# servopoinB-2.net
KiCad netlist of a schematic drawn in EAGLE
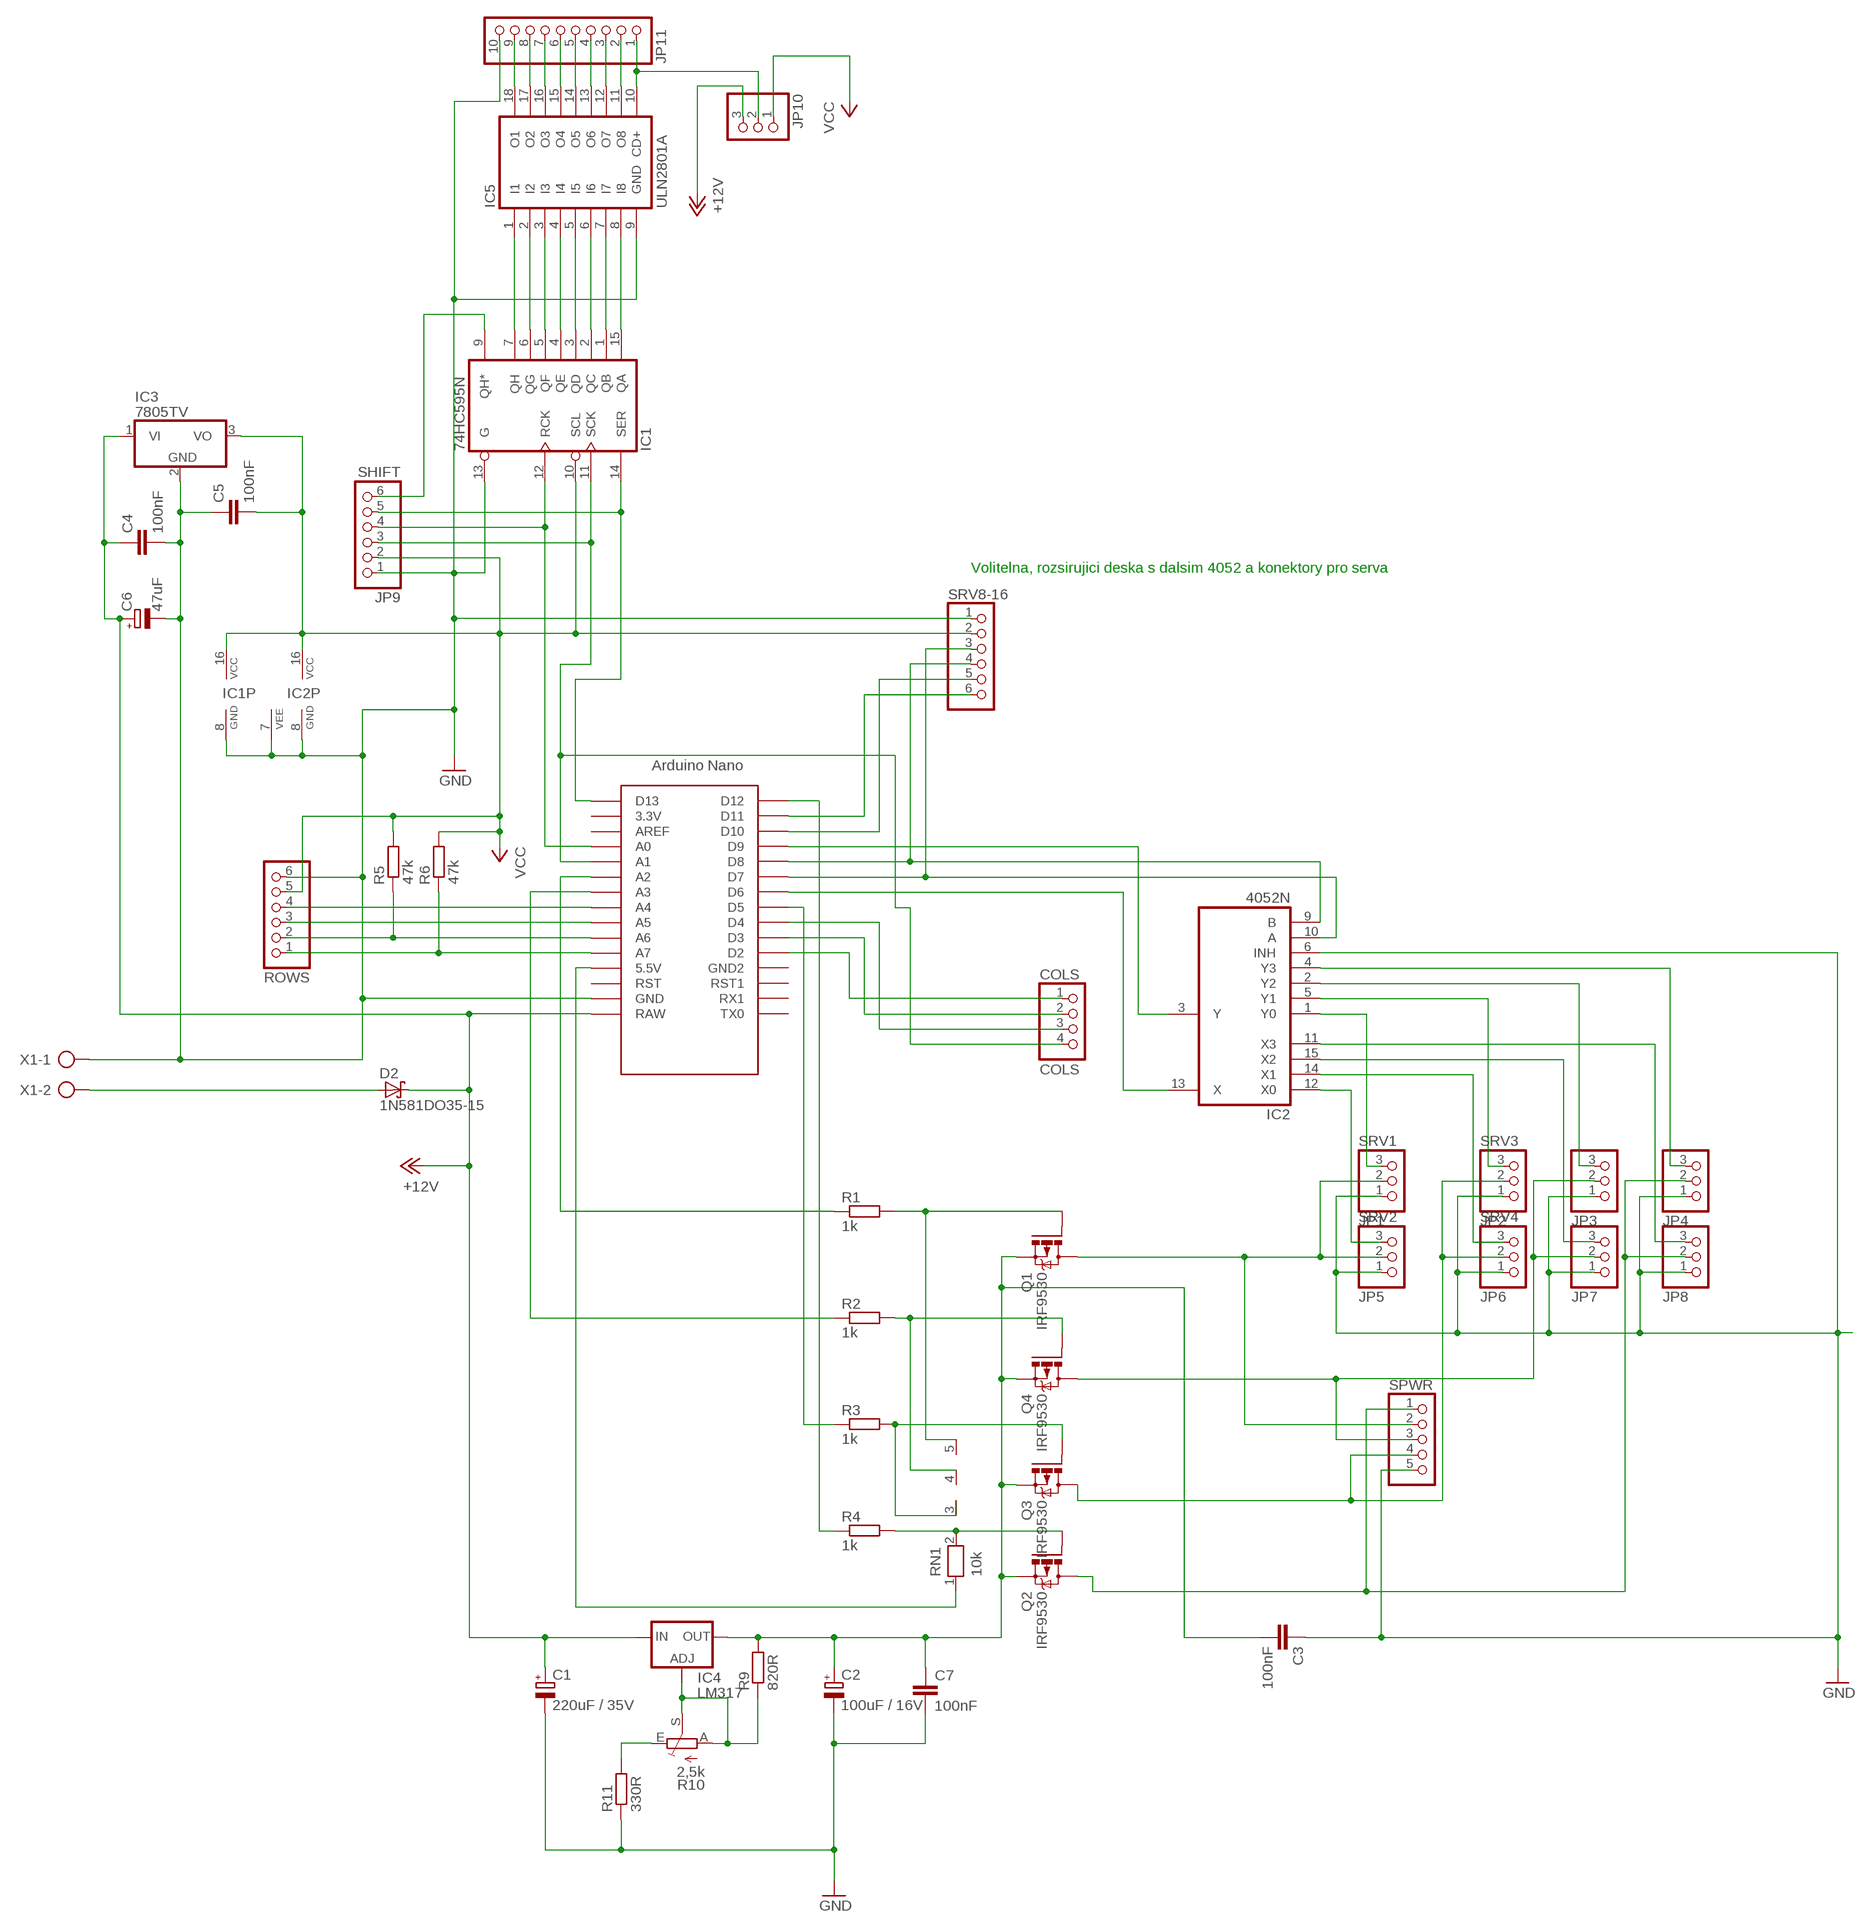
[diagram p0: schematic, sheet 1]

(export (version "E")
  (design (tool "Eeschema 10.0.6"))
  (components
    (comp (ref "C1")
      (value "220uF / 35V")
      (footprint "eagle-import:E5-10,5")
      (libsource (lib "eagle-import") (part "resistor_CPOL-EUE5-10.5"))
    )
    (comp (ref "C2")
      (value "100uF / 16V")
      (footprint "eagle-import:E2,5-5")
      (libsource (lib "eagle-import") (part "resistor_CPOL-EUE2.5-5"))
    )
    (comp (ref "C3")
      (value "100nF")
      (footprint "eagle-import:C025-025X050")
      (libsource (lib "eagle-import") (part "resistor_C-EU025-025X050"))
    )
    (comp (ref "C4")
      (value "100nF")
      (footprint "eagle-import:C025-025X050")
      (libsource (lib "eagle-import") (part "C-EU025-025X050"))
    )
    (comp (ref "C5")
      (value "100nF")
      (footprint "eagle-import:C025-025X050")
      (libsource (lib "eagle-import") (part "C-EU025-025X050"))
    )
    (comp (ref "C6")
      (value "47uF")
      (footprint "eagle-import:E2,5-6")
      (libsource (lib "eagle-import") (part "CPOL-EUE2.5-6"))
    )
    (comp (ref "C7")
      (value "100nF")
      (footprint "eagle-import:C025-025X050")
      (libsource (lib "eagle-import") (part "resistor_C-EU025-025X050"))
    )
    (comp (ref "COLS")
      (value "COLS")
      (footprint "eagle-import:1X04")
      (libsource (lib "eagle-import") (part "PINHD-1X4"))
    )
    (comp (ref "D2")
      (value "1N581DO35-15")
      (footprint "eagle-import:DO35-10")
      (libsource (lib "eagle-import") (part "1N581DO35-15"))
    )
    (comp (ref "IC1")
      (value "74HC595N")
      (footprint "eagle-import:DIL16")
      (libsource (lib "eagle-import") (part "74595NHC"))
    )
    (comp (ref "IC2")
      (value "4052N")
      (footprint "eagle-import:DIL16")
      (libsource (lib "eagle-import") (part "4052N"))
    )
    (comp (ref "IC3")
      (value "7805TV")
      (footprint "eagle-import:TO220V")
      (libsource (lib "eagle-import") (part "78TV05"))
    )
    (comp (ref "IC4")
      (value "LM317")
      (footprint "eagle-import:317TS")
      (libsource (lib "eagle-import") (part "LM317TS"))
    )
    (comp (ref "IC5")
      (value "ULN2801A")
      (footprint "eagle-import:DIL18")
      (libsource (lib "eagle-import") (part "ULN2801A"))
    )
    (comp (ref "JP1")
      (value "SRV1")
      (footprint "eagle-import:1X03")
      (libsource (lib "eagle-import") (part "PINHD-1X3"))
    )
    (comp (ref "JP2")
      (value "SRV3")
      (footprint "eagle-import:1X03")
      (libsource (lib "eagle-import") (part "PINHD-1X3"))
    )
    (comp (ref "JP3")
      (value "PINHD-1X3")
      (footprint "eagle-import:1X03")
      (libsource (lib "eagle-import") (part "PINHD-1X3"))
    )
    (comp (ref "JP4")
      (value "PINHD-1X3")
      (footprint "eagle-import:1X03")
      (libsource (lib "eagle-import") (part "PINHD-1X3"))
    )
    (comp (ref "JP5")
      (value "SRV2")
      (footprint "eagle-import:1X03")
      (libsource (lib "eagle-import") (part "PINHD-1X3"))
    )
    (comp (ref "JP6")
      (value "SRV4")
      (footprint "eagle-import:1X03")
      (libsource (lib "eagle-import") (part "PINHD-1X3"))
    )
    (comp (ref "JP7")
      (value "PINHD-1X3")
      (footprint "eagle-import:1X03")
      (libsource (lib "eagle-import") (part "PINHD-1X3"))
    )
    (comp (ref "JP8")
      (value "PINHD-1X3")
      (footprint "eagle-import:1X03")
      (libsource (lib "eagle-import") (part "PINHD-1X3"))
    )
    (comp (ref "JP9")
      (value "SHIFT")
      (footprint "eagle-import:1X06")
      (libsource (lib "eagle-import") (part "PINHD-1X6"))
    )
    (comp (ref "JP10")
      (value "PINHD-1X3")
      (footprint "eagle-import:1X03")
      (libsource (lib "eagle-import") (part "PINHD-1X3"))
    )
    (comp (ref "JP11")
      (value "PINHD-1X10")
      (footprint "eagle-import:1X10")
      (libsource (lib "eagle-import") (part "PINHD-1X10"))
    )
    (comp (ref "Q1")
      (value "IRF9530")
      (footprint "eagle-import:TO220BV")
      (libsource (lib "eagle-import") (part "IRF9530"))
    )
    (comp (ref "Q2")
      (value "IRF9530")
      (footprint "eagle-import:TO220BV")
      (libsource (lib "eagle-import") (part "IRF9530"))
    )
    (comp (ref "Q3")
      (value "IRF9530")
      (footprint "eagle-import:TO220BV")
      (libsource (lib "eagle-import") (part "IRF9530"))
    )
    (comp (ref "Q4")
      (value "IRF9530")
      (footprint "eagle-import:TO220BV")
      (libsource (lib "eagle-import") (part "IRF9530"))
    )
    (comp (ref "R1")
      (value "1k")
      (footprint "eagle-import:0207_10")
      (libsource (lib "eagle-import") (part "R-EU_0207/10"))
    )
    (comp (ref "R2")
      (value "1k")
      (footprint "eagle-import:0207_10")
      (libsource (lib "eagle-import") (part "R-EU_0207/10"))
    )
    (comp (ref "R3")
      (value "1k")
      (footprint "eagle-import:0207_10")
      (libsource (lib "eagle-import") (part "R-EU_0207/10"))
    )
    (comp (ref "R4")
      (value "1k")
      (footprint "eagle-import:0207_10")
      (libsource (lib "eagle-import") (part "R-EU_0207/10"))
    )
    (comp (ref "R5")
      (value "47k")
      (footprint "eagle-import:0207_10")
      (libsource (lib "eagle-import") (part "R-EU_0207/10"))
    )
    (comp (ref "R6")
      (value "47k")
      (footprint "eagle-import:0207_10")
      (libsource (lib "eagle-import") (part "R-EU_0207/10"))
    )
    (comp (ref "R9")
      (value "820R")
      (footprint "eagle-import:0207_10")
      (libsource (lib "eagle-import") (part "R-EU_0207/10"))
    )
    (comp (ref "R10")
      (value "2,5k")
      (footprint "eagle-import:LI10")
      (libsource (lib "eagle-import") (part "TRIM_EU-LI10-PADS"))
    )
    (comp (ref "R11")
      (value "330R")
      (footprint "eagle-import:0207_10")
      (libsource (lib "eagle-import") (part "R-EU_0207/10"))
    )
    (comp (ref "RN1")
      (value "10k")
      (footprint "eagle-import:RN-5")
      (libsource (lib "eagle-import") (part "RN04"))
    )
    (comp (ref "ROWS")
      (value "PINHD-1X6")
      (footprint "eagle-import:1X06")
      (libsource (lib "eagle-import") (part "PINHD-1X6"))
    )
    (comp (ref "SPWR")
      (value "PINHD-1X5")
      (footprint "eagle-import:1X05")
      (libsource (lib "eagle-import") (part "PINHD-1X5"))
    )
    (comp (ref "SRV8-16")
      (value "PINHD-1X6")
      (footprint "eagle-import:1X06")
      (libsource (lib "eagle-import") (part "PINHD-1X6"))
    )
    (comp (ref "U$1")
      (value "NANO")
      (footprint "eagle-import:NANO")
      (libsource (lib "eagle-import") (part "NANO"))
    )
    (comp (ref "X1")
      (value "AK500/2")
      (footprint "eagle-import:AK500_2")
      (libsource (lib "eagle-import") (part "AK500/2"))
    )
  )
  (nets
    (net (code "1") (name "+12V") (class "Default")
      (node (ref "C1") (pin "+") (pinfunction "+_+") (pintype "passive"))
      (node (ref "C4") (pin "1") (pinfunction "1_1") (pintype "passive"))
      (node (ref "C6") (pin "+") (pinfunction "+_+") (pintype "passive"))
      (node (ref "D2") (pin "C") (pinfunction "C_C") (pintype "passive"))
      (node (ref "IC3") (pin "1") (pinfunction "VI_1") (pintype "input"))
      (node (ref "IC4") (pin "3") (pinfunction "IN_3") (pintype "input"))
      (node (ref "JP10") (pin "3") (pinfunction "3_3") (pintype "passive"))
      (node (ref "U$1") (pin "RAW") (pinfunction "RAW_RAW") (pintype "bidirectional"))
    )
    (net (code "2") (name "GND") (class "Default")
      (node (ref "C1") (pin "-") (pinfunction "-_-") (pintype "passive"))
      (node (ref "C2") (pin "-") (pinfunction "-_-") (pintype "passive"))
      (node (ref "C3") (pin "1") (pinfunction "1_1") (pintype "passive"))
      (node (ref "C4") (pin "2") (pinfunction "2_2") (pintype "passive"))
      (node (ref "C5") (pin "1") (pinfunction "1_1") (pintype "passive"))
      (node (ref "C6") (pin "-") (pinfunction "-_-") (pintype "passive"))
      (node (ref "C7") (pin "2") (pinfunction "2_2") (pintype "passive"))
      (node (ref "IC1") (pin "13") (pinfunction "G_13") (pintype "input"))
      (node (ref "IC1") (pin "8") (pinfunction "GND_8") (pintype "power_in"))
      (node (ref "IC2") (pin "6") (pinfunction "INH_6") (pintype "input"))
      (node (ref "IC2") (pin "7") (pinfunction "VEE_7") (pintype "power_in"))
      (node (ref "IC2") (pin "8") (pinfunction "GND_8") (pintype "power_in"))
      (node (ref "IC3") (pin "2") (pinfunction "GND_2") (pintype "passive"))
      (node (ref "IC5") (pin "9") (pinfunction "GND_9") (pintype "power_in"))
      (node (ref "JP1") (pin "1") (pinfunction "1_1") (pintype "passive"))
      (node (ref "JP11") (pin "10") (pinfunction "10_10") (pintype "passive"))
      (node (ref "JP2") (pin "1") (pinfunction "1_1") (pintype "passive"))
      (node (ref "JP3") (pin "1") (pinfunction "1_1") (pintype "passive"))
      (node (ref "JP4") (pin "1") (pinfunction "1_1") (pintype "passive"))
      (node (ref "JP5") (pin "1") (pinfunction "1_1") (pintype "passive"))
      (node (ref "JP6") (pin "1") (pinfunction "1_1") (pintype "passive"))
      (node (ref "JP7") (pin "1") (pinfunction "1_1") (pintype "passive"))
      (node (ref "JP8") (pin "1") (pinfunction "1_1") (pintype "passive"))
      (node (ref "JP9") (pin "1") (pinfunction "1_1") (pintype "passive"))
      (node (ref "R11") (pin "1") (pinfunction "1_1") (pintype "passive"))
      (node (ref "ROWS") (pin "6") (pinfunction "6_6") (pintype "passive"))
      (node (ref "SPWR") (pin "5") (pinfunction "5_5") (pintype "passive"))
      (node (ref "SRV8-16") (pin "1") (pinfunction "1_1") (pintype "passive"))
      (node (ref "U$1") (pin "GND") (pinfunction "GND_GND") (pintype "bidirectional"))
      (node (ref "X1") (pin "1") (pinfunction "KL_1") (pintype "passive"))
    )
    (net (code "3") (name "Net-(COLS-Pad1)") (class "Default")
      (node (ref "COLS") (pin "1") (pinfunction "1_1") (pintype "passive"))
      (node (ref "U$1") (pin "D2") (pinfunction "D2_D2") (pintype "bidirectional"))
    )
    (net (code "4") (name "Net-(COLS-Pad2)") (class "Default")
      (node (ref "COLS") (pin "2") (pinfunction "2_2") (pintype "passive"))
      (node (ref "U$1") (pin "D3") (pinfunction "D3_D3") (pintype "bidirectional"))
    )
    (net (code "5") (name "Net-(COLS-Pad3)") (class "Default")
      (node (ref "COLS") (pin "3") (pinfunction "3_3") (pintype "passive"))
      (node (ref "U$1") (pin "D4") (pinfunction "D4_D4") (pintype "bidirectional"))
    )
    (net (code "6") (name "Net-(IC1A-QA)") (class "Default")
      (node (ref "IC1") (pin "15") (pinfunction "QA_15") (pintype "tri_state"))
      (node (ref "IC5") (pin "8") (pinfunction "I8_8") (pintype "input"))
    )
    (net (code "7") (name "Net-(IC1A-QB)") (class "Default")
      (node (ref "IC1") (pin "1") (pinfunction "QB_1") (pintype "tri_state"))
      (node (ref "IC5") (pin "7") (pinfunction "I7_7") (pintype "input"))
    )
    (net (code "8") (name "Net-(IC1A-QC)") (class "Default")
      (node (ref "IC1") (pin "2") (pinfunction "QC_2") (pintype "tri_state"))
      (node (ref "IC5") (pin "6") (pinfunction "I6_6") (pintype "input"))
    )
    (net (code "9") (name "Net-(IC1A-QD)") (class "Default")
      (node (ref "IC1") (pin "3") (pinfunction "QD_3") (pintype "tri_state"))
      (node (ref "IC5") (pin "5") (pinfunction "I5_5") (pintype "input"))
    )
    (net (code "10") (name "Net-(IC1A-QE)") (class "Default")
      (node (ref "IC1") (pin "4") (pinfunction "QE_4") (pintype "tri_state"))
      (node (ref "IC5") (pin "4") (pinfunction "I4_4") (pintype "input"))
    )
    (net (code "11") (name "Net-(IC1A-QF)") (class "Default")
      (node (ref "IC1") (pin "5") (pinfunction "QF_5") (pintype "tri_state"))
      (node (ref "IC5") (pin "3") (pinfunction "I3_3") (pintype "input"))
    )
    (net (code "12") (name "Net-(IC1A-QG)") (class "Default")
      (node (ref "IC1") (pin "6") (pinfunction "QG_6") (pintype "tri_state"))
      (node (ref "IC5") (pin "2") (pinfunction "I2_2") (pintype "input"))
    )
    (net (code "13") (name "Net-(IC1A-QH)") (class "Default")
      (node (ref "IC1") (pin "7") (pinfunction "QH_7") (pintype "tri_state"))
      (node (ref "IC5") (pin "1") (pinfunction "I1_1") (pintype "input"))
    )
    (net (code "14") (name "Net-(IC1A-QH*)") (class "Default")
      (node (ref "IC1") (pin "9") (pinfunction "QH*_9") (pintype "tri_state"))
      (node (ref "JP9") (pin "6") (pinfunction "6_6") (pintype "passive"))
    )
    (net (code "15") (name "Net-(IC1A-RCK)") (class "Default")
      (node (ref "IC1") (pin "12") (pinfunction "RCK_12") (pintype "input"))
      (node (ref "JP9") (pin "4") (pinfunction "4_4") (pintype "passive"))
      (node (ref "U$1") (pin "A0") (pinfunction "A0_A0") (pintype "bidirectional"))
    )
    (net (code "16") (name "Net-(IC1A-SCK)") (class "Default")
      (node (ref "COLS") (pin "4") (pinfunction "4_4") (pintype "passive"))
      (node (ref "IC1") (pin "11") (pinfunction "SCK_11") (pintype "input"))
      (node (ref "JP9") (pin "3") (pinfunction "3_3") (pintype "passive"))
      (node (ref "U$1") (pin "A1") (pinfunction "A1_A1") (pintype "bidirectional"))
    )
    (net (code "17") (name "Net-(IC1A-SER)") (class "Default")
      (node (ref "IC1") (pin "14") (pinfunction "SER_14") (pintype "input"))
      (node (ref "JP9") (pin "5") (pinfunction "5_5") (pintype "passive"))
      (node (ref "U$1") (pin "D13") (pinfunction "D13_D13") (pintype "bidirectional"))
    )
    (net (code "18") (name "Net-(IC2A-A)") (class "Default")
      (node (ref "IC2") (pin "10") (pinfunction "A_10") (pintype "input"))
      (node (ref "SRV8-16") (pin "3") (pinfunction "3_3") (pintype "passive"))
      (node (ref "U$1") (pin "D7") (pinfunction "D7_D7") (pintype "bidirectional"))
    )
    (net (code "19") (name "Net-(IC2A-B)") (class "Default")
      (node (ref "IC2") (pin "9") (pinfunction "B_9") (pintype "input"))
      (node (ref "SRV8-16") (pin "4") (pinfunction "4_4") (pintype "passive"))
      (node (ref "U$1") (pin "D8") (pinfunction "D8_D8") (pintype "bidirectional"))
    )
    (net (code "20") (name "Net-(IC2A-X)") (class "Default")
      (node (ref "IC2") (pin "13") (pinfunction "X_13") (pintype "bidirectional"))
      (node (ref "U$1") (pin "D6") (pinfunction "D6_D6") (pintype "bidirectional"))
    )
    (net (code "21") (name "Net-(IC2A-X0)") (class "Default")
      (node (ref "IC2") (pin "12") (pinfunction "X0_12") (pintype "bidirectional"))
      (node (ref "JP5") (pin "3") (pinfunction "3_3") (pintype "passive"))
    )
    (net (code "22") (name "Net-(IC2A-X1)") (class "Default")
      (node (ref "IC2") (pin "14") (pinfunction "X1_14") (pintype "bidirectional"))
      (node (ref "JP6") (pin "3") (pinfunction "3_3") (pintype "passive"))
    )
    (net (code "23") (name "Net-(IC2A-X2)") (class "Default")
      (node (ref "IC2") (pin "15") (pinfunction "X2_15") (pintype "bidirectional"))
      (node (ref "JP7") (pin "3") (pinfunction "3_3") (pintype "passive"))
    )
    (net (code "24") (name "Net-(IC2A-X3)") (class "Default")
      (node (ref "IC2") (pin "11") (pinfunction "X3_11") (pintype "bidirectional"))
      (node (ref "JP8") (pin "3") (pinfunction "3_3") (pintype "passive"))
    )
    (net (code "25") (name "Net-(IC2A-Y)") (class "Default")
      (node (ref "IC2") (pin "3") (pinfunction "Y_3") (pintype "bidirectional"))
      (node (ref "U$1") (pin "D9") (pinfunction "D9_D9") (pintype "bidirectional"))
    )
    (net (code "26") (name "Net-(IC2A-Y0)") (class "Default")
      (node (ref "IC2") (pin "1") (pinfunction "Y0_1") (pintype "bidirectional"))
      (node (ref "JP1") (pin "3") (pinfunction "3_3") (pintype "passive"))
    )
    (net (code "27") (name "Net-(IC2A-Y1)") (class "Default")
      (node (ref "IC2") (pin "5") (pinfunction "Y1_5") (pintype "bidirectional"))
      (node (ref "JP2") (pin "3") (pinfunction "3_3") (pintype "passive"))
    )
    (net (code "28") (name "Net-(IC2A-Y2)") (class "Default")
      (node (ref "IC2") (pin "2") (pinfunction "Y2_2") (pintype "bidirectional"))
      (node (ref "JP3") (pin "3") (pinfunction "3_3") (pintype "passive"))
    )
    (net (code "29") (name "Net-(IC2A-Y3)") (class "Default")
      (node (ref "IC2") (pin "4") (pinfunction "Y3_4") (pintype "bidirectional"))
      (node (ref "JP4") (pin "3") (pinfunction "3_3") (pintype "passive"))
    )
    (net (code "30") (name "Net-(IC4-ADJ)") (class "Default")
      (node (ref "IC4") (pin "1") (pinfunction "ADJ_1") (pintype "input"))
      (node (ref "R10") (pin "A") (pinfunction "A_A") (pintype "passive"))
      (node (ref "R10") (pin "S") (pinfunction "S_S") (pintype "passive"))
      (node (ref "R9") (pin "1") (pinfunction "1_1") (pintype "passive"))
    )
    (net (code "31") (name "Net-(IC4-OUT)") (class "Default")
      (node (ref "C2") (pin "+") (pinfunction "+_+") (pintype "passive"))
      (node (ref "C3") (pin "2") (pinfunction "2_2") (pintype "passive"))
      (node (ref "C7") (pin "1") (pinfunction "1_1") (pintype "passive"))
      (node (ref "IC4") (pin "2") (pinfunction "OUT_2") (pintype "passive"))
      (node (ref "Q1") (pin "S") (pinfunction "S_S") (pintype "passive"))
      (node (ref "Q2") (pin "S") (pinfunction "S_S") (pintype "passive"))
      (node (ref "Q3") (pin "S") (pinfunction "S_S") (pintype "passive"))
      (node (ref "Q4") (pin "S") (pinfunction "S_S") (pintype "passive"))
      (node (ref "R9") (pin "2") (pinfunction "2_2") (pintype "passive"))
    )
    (net (code "32") (name "Net-(IC5-CD+)") (class "Default")
      (node (ref "IC5") (pin "10") (pinfunction "CD+_10") (pintype "passive"))
      (node (ref "JP10") (pin "2") (pinfunction "2_2") (pintype "passive"))
      (node (ref "JP11") (pin "1") (pinfunction "1_1") (pintype "passive"))
    )
    (net (code "33") (name "Net-(IC5-O1)") (class "Default")
      (node (ref "IC5") (pin "18") (pinfunction "O1_18") (pintype "open_collector"))
      (node (ref "JP11") (pin "9") (pinfunction "9_9") (pintype "passive"))
    )
    (net (code "34") (name "Net-(IC5-O2)") (class "Default")
      (node (ref "IC5") (pin "17") (pinfunction "O2_17") (pintype "open_collector"))
      (node (ref "JP11") (pin "8") (pinfunction "8_8") (pintype "passive"))
    )
    (net (code "35") (name "Net-(IC5-O3)") (class "Default")
      (node (ref "IC5") (pin "16") (pinfunction "O3_16") (pintype "open_collector"))
      (node (ref "JP11") (pin "7") (pinfunction "7_7") (pintype "passive"))
    )
    (net (code "36") (name "Net-(IC5-O4)") (class "Default")
      (node (ref "IC5") (pin "15") (pinfunction "O4_15") (pintype "open_collector"))
      (node (ref "JP11") (pin "6") (pinfunction "6_6") (pintype "passive"))
    )
    (net (code "37") (name "Net-(IC5-O5)") (class "Default")
      (node (ref "IC5") (pin "14") (pinfunction "O5_14") (pintype "open_collector"))
      (node (ref "JP11") (pin "5") (pinfunction "5_5") (pintype "passive"))
    )
    (net (code "38") (name "Net-(IC5-O6)") (class "Default")
      (node (ref "IC5") (pin "13") (pinfunction "O6_13") (pintype "open_collector"))
      (node (ref "JP11") (pin "4") (pinfunction "4_4") (pintype "passive"))
    )
    (net (code "39") (name "Net-(IC5-O7)") (class "Default")
      (node (ref "IC5") (pin "12") (pinfunction "O7_12") (pintype "open_collector"))
      (node (ref "JP11") (pin "3") (pinfunction "3_3") (pintype "passive"))
    )
    (net (code "40") (name "Net-(IC5-O8)") (class "Default")
      (node (ref "IC5") (pin "11") (pinfunction "O8_11") (pintype "open_collector"))
      (node (ref "JP11") (pin "2") (pinfunction "2_2") (pintype "passive"))
    )
    (net (code "41") (name "Net-(JP1-Pad2)") (class "Default")
      (node (ref "JP1") (pin "2") (pinfunction "2_2") (pintype "passive"))
      (node (ref "JP5") (pin "2") (pinfunction "2_2") (pintype "passive"))
      (node (ref "Q1") (pin "D") (pinfunction "D_D") (pintype "passive"))
      (node (ref "SPWR") (pin "2") (pinfunction "2_2") (pintype "passive"))
    )
    (net (code "42") (name "Net-(JP2-Pad2)") (class "Default")
      (node (ref "JP2") (pin "2") (pinfunction "2_2") (pintype "passive"))
      (node (ref "JP6") (pin "2") (pinfunction "2_2") (pintype "passive"))
      (node (ref "Q3") (pin "D") (pinfunction "D_D") (pintype "passive"))
      (node (ref "SPWR") (pin "4") (pinfunction "4_4") (pintype "passive"))
    )
    (net (code "43") (name "Net-(JP3-Pad2)") (class "Default")
      (node (ref "JP3") (pin "2") (pinfunction "2_2") (pintype "passive"))
      (node (ref "JP7") (pin "2") (pinfunction "2_2") (pintype "passive"))
      (node (ref "Q4") (pin "D") (pinfunction "D_D") (pintype "passive"))
      (node (ref "SPWR") (pin "3") (pinfunction "3_3") (pintype "passive"))
    )
    (net (code "44") (name "Net-(JP4-Pad2)") (class "Default")
      (node (ref "JP4") (pin "2") (pinfunction "2_2") (pintype "passive"))
      (node (ref "JP8") (pin "2") (pinfunction "2_2") (pintype "passive"))
      (node (ref "Q2") (pin "D") (pinfunction "D_D") (pintype "passive"))
      (node (ref "SPWR") (pin "1") (pinfunction "1_1") (pintype "passive"))
    )
    (net (code "45") (name "Net-(Q1-PadG)") (class "Default")
      (node (ref "Q1") (pin "G") (pinfunction "G_G") (pintype "passive"))
      (node (ref "R1") (pin "2") (pinfunction "2_2") (pintype "passive"))
      (node (ref "RN1") (pin "5") (pinfunction "5_5") (pintype "passive"))
    )
    (net (code "46") (name "Net-(Q2-PadG)") (class "Default")
      (node (ref "Q2") (pin "G") (pinfunction "G_G") (pintype "passive"))
      (node (ref "R4") (pin "2") (pinfunction "2_2") (pintype "passive"))
      (node (ref "RN1") (pin "2") (pinfunction "2_2") (pintype "passive"))
    )
    (net (code "47") (name "Net-(Q3-PadG)") (class "Default")
      (node (ref "Q3") (pin "G") (pinfunction "G_G") (pintype "passive"))
      (node (ref "R3") (pin "2") (pinfunction "2_2") (pintype "passive"))
      (node (ref "RN1") (pin "3") (pinfunction "3_3") (pintype "passive"))
    )
    (net (code "48") (name "Net-(Q4-PadG)") (class "Default")
      (node (ref "Q4") (pin "G") (pinfunction "G_G") (pintype "passive"))
      (node (ref "R2") (pin "2") (pinfunction "2_2") (pintype "passive"))
      (node (ref "RN1") (pin "4") (pinfunction "4_4") (pintype "passive"))
    )
    (net (code "49") (name "Net-(R1-Pad1)") (class "Default")
      (node (ref "R1") (pin "1") (pinfunction "1_1") (pintype "passive"))
      (node (ref "U$1") (pin "A2") (pinfunction "A2_A2") (pintype "bidirectional"))
    )
    (net (code "50") (name "Net-(R2-Pad1)") (class "Default")
      (node (ref "R2") (pin "1") (pinfunction "1_1") (pintype "passive"))
      (node (ref "U$1") (pin "A3") (pinfunction "A3_A3") (pintype "bidirectional"))
    )
    (net (code "51") (name "Net-(R3-Pad1)") (class "Default")
      (node (ref "R3") (pin "1") (pinfunction "1_1") (pintype "passive"))
      (node (ref "U$1") (pin "D5") (pinfunction "D5_D5") (pintype "bidirectional"))
    )
    (net (code "52") (name "Net-(R4-Pad1)") (class "Default")
      (node (ref "R4") (pin "1") (pinfunction "1_1") (pintype "passive"))
      (node (ref "U$1") (pin "D12") (pinfunction "D12_D12") (pintype "bidirectional"))
    )
    (net (code "53") (name "Net-(R5-Pad1)") (class "Default")
      (node (ref "R5") (pin "1") (pinfunction "1_1") (pintype "passive"))
      (node (ref "ROWS") (pin "2") (pinfunction "2_2") (pintype "passive"))
      (node (ref "U$1") (pin "A6") (pinfunction "A6_A6") (pintype "bidirectional"))
    )
    (net (code "54") (name "Net-(R6-Pad1)") (class "Default")
      (node (ref "R6") (pin "1") (pinfunction "1_1") (pintype "passive"))
      (node (ref "ROWS") (pin "1") (pinfunction "1_1") (pintype "passive"))
      (node (ref "U$1") (pin "A7") (pinfunction "A7_A7") (pintype "bidirectional"))
    )
    (net (code "55") (name "Net-(R10-PadE)") (class "Default")
      (node (ref "R10") (pin "E") (pinfunction "E_E") (pintype "passive"))
      (node (ref "R11") (pin "2") (pinfunction "2_2") (pintype "passive"))
    )
    (net (code "56") (name "Net-(ROWS-Pad3)") (class "Default")
      (node (ref "ROWS") (pin "3") (pinfunction "3_3") (pintype "passive"))
      (node (ref "U$1") (pin "A5") (pinfunction "A5_A5") (pintype "bidirectional"))
    )
    (net (code "57") (name "Net-(ROWS-Pad4)") (class "Default")
      (node (ref "ROWS") (pin "4") (pinfunction "4_4") (pintype "passive"))
      (node (ref "U$1") (pin "A4") (pinfunction "A4_A4") (pintype "bidirectional"))
    )
    (net (code "58") (name "Net-(SRV8-16-Pad5)") (class "Default")
      (node (ref "SRV8-16") (pin "5") (pinfunction "5_5") (pintype "passive"))
      (node (ref "U$1") (pin "D10") (pinfunction "D10_D10") (pintype "bidirectional"))
    )
    (net (code "59") (name "Net-(SRV8-16-Pad6)") (class "Default")
      (node (ref "SRV8-16") (pin "6") (pinfunction "6_6") (pintype "passive"))
      (node (ref "U$1") (pin "D11") (pinfunction "D11_D11") (pintype "bidirectional"))
    )
    (net (code "60") (name "Net-(U$1-5.5V)") (class "Default")
      (node (ref "RN1") (pin "1") (pinfunction "1_1") (pintype "passive"))
      (node (ref "U$1") (pin "5V") (pinfunction "5.5V_5V") (pintype "bidirectional"))
    )
    (net (code "61") (name "Net-(X1B-KL)") (class "Default")
      (node (ref "D2") (pin "A") (pinfunction "A_A") (pintype "passive"))
      (node (ref "X1") (pin "2") (pinfunction "KL_2") (pintype "passive"))
    )
    (net (code "62") (name "VCC") (class "Default")
      (node (ref "C5") (pin "2") (pinfunction "2_2") (pintype "passive"))
      (node (ref "IC1") (pin "10") (pinfunction "SCL_10") (pintype "input"))
      (node (ref "IC1") (pin "16") (pinfunction "VCC_16") (pintype "power_in"))
      (node (ref "IC2") (pin "16") (pinfunction "VCC_16") (pintype "power_in"))
      (node (ref "IC3") (pin "3") (pinfunction "VO_3") (pintype "passive"))
      (node (ref "JP10") (pin "1") (pinfunction "1_1") (pintype "passive"))
      (node (ref "JP9") (pin "2") (pinfunction "2_2") (pintype "passive"))
      (node (ref "R5") (pin "2") (pinfunction "2_2") (pintype "passive"))
      (node (ref "R6") (pin "2") (pinfunction "2_2") (pintype "passive"))
      (node (ref "ROWS") (pin "5") (pinfunction "5_5") (pintype "passive"))
      (node (ref "SRV8-16") (pin "2") (pinfunction "2_2") (pintype "passive"))
    )
    (net (code "63") (name "unconnected-(U$1-GND2-PadGND1)") (class "Default")
      (node (ref "U$1") (pin "GND1") (pinfunction "GND2_GND1") (pintype "bidirectional"))
    )
    (net (code "64") (name "unconnected-(U$1-Pad3.3V)") (class "Default")
      (node (ref "U$1") (pin "3.3V") (pinfunction "3.3V_3.3V") (pintype "bidirectional"))
    )
    (net (code "65") (name "unconnected-(U$1-PadAREF)") (class "Default")
      (node (ref "U$1") (pin "AREF") (pinfunction "AREF_AREF") (pintype "bidirectional"))
    )
    (net (code "66") (name "unconnected-(U$1-PadICSP1)") (class "Default")
      (node (ref "U$1") (pin "ICSP1") (pinfunction "ICSP1_ICSP1") (pintype "bidirectional"))
    )
    (net (code "67") (name "unconnected-(U$1-PadICSP2)") (class "Default")
      (node (ref "U$1") (pin "ICSP2") (pinfunction "ICSP2_ICSP2") (pintype "bidirectional"))
    )
    (net (code "68") (name "unconnected-(U$1-PadICSP3)") (class "Default")
      (node (ref "U$1") (pin "ICSP3") (pinfunction "ICSP3_ICSP3") (pintype "bidirectional"))
    )
    (net (code "69") (name "unconnected-(U$1-PadICSP4)") (class "Default")
      (node (ref "U$1") (pin "ICSP4") (pinfunction "ICSP4_ICSP4") (pintype "bidirectional"))
    )
    (net (code "70") (name "unconnected-(U$1-PadICSP5)") (class "Default")
      (node (ref "U$1") (pin "ICSP5") (pinfunction "ICSP5_ICSP5") (pintype "bidirectional"))
    )
    (net (code "71") (name "unconnected-(U$1-PadICSP6)") (class "Default")
      (node (ref "U$1") (pin "ICSP6") (pinfunction "ICSP6_ICSP6") (pintype "bidirectional"))
    )
    (net (code "72") (name "unconnected-(U$1-PadRST)") (class "Default")
      (node (ref "U$1") (pin "RST") (pinfunction "RST_RST") (pintype "bidirectional"))
    )
    (net (code "73") (name "unconnected-(U$1-PadRST1)") (class "Default")
      (node (ref "U$1") (pin "RST1") (pinfunction "RST1_RST1") (pintype "bidirectional"))
    )
    (net (code "74") (name "unconnected-(U$1-PadRX1)") (class "Default")
      (node (ref "U$1") (pin "RX1") (pinfunction "RX1_RX1") (pintype "bidirectional"))
    )
    (net (code "75") (name "unconnected-(U$1-PadTX0)") (class "Default")
      (node (ref "U$1") (pin "TX0") (pinfunction "TX0_TX0") (pintype "bidirectional"))
    )
  )
)
